# zero_board.net
KiCad netlist of a schematic drawn in EAGLE
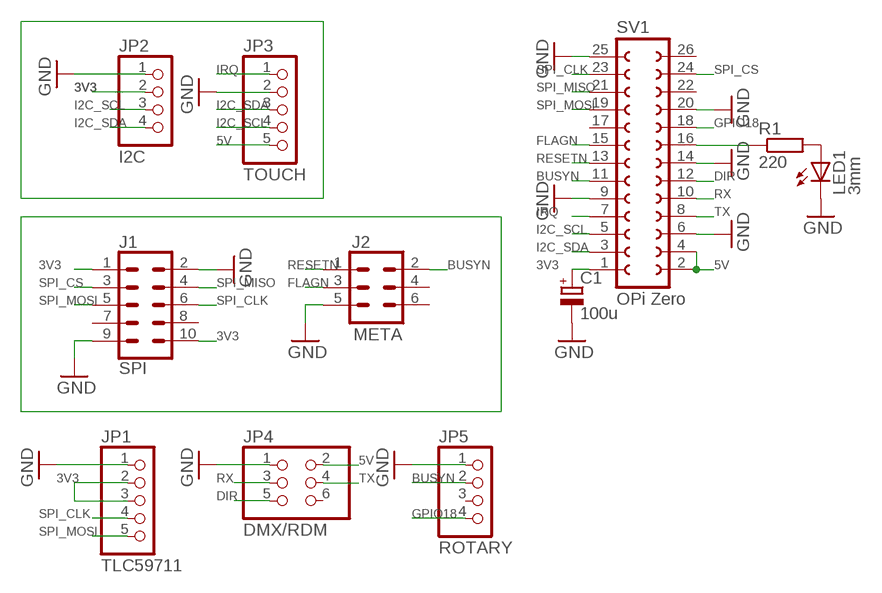
[diagram p0: schematic, sheet 1]

(export (version "E")
  (design (tool "Eeschema 10.0.6"))
  (components
    (comp (ref "C1")
      (value "100u")
      (footprint "eagle-import:E2,5-6")
      (libsource (lib "eagle-import") (part "CPOL-EUE2.5-6"))
    )
    (comp (ref "J1")
      (value "SPI")
      (footprint "eagle-import:2X5-SHROUDED")
      (libsource (lib "eagle-import") (part "CONN_05X2SHD"))
    )
    (comp (ref "J2")
      (value "META")
      (footprint "eagle-import:2X3-SHROUDED")
      (libsource (lib "eagle-import") (part "CONN_03X2SHROUD"))
    )
    (comp (ref "JP1")
      (value "TLC59711")
      (footprint "eagle-import:1X05")
      (libsource (lib "eagle-import") (part "PINHD-1X5"))
    )
    (comp (ref "JP2")
      (value "I2C")
      (footprint "eagle-import:1X04")
      (libsource (lib "eagle-import") (part "PINHD-1X4"))
    )
    (comp (ref "JP3")
      (value "TOUCH")
      (footprint "eagle-import:1X05")
      (libsource (lib "eagle-import") (part "PINHD-1X5"))
    )
    (comp (ref "JP4")
      (value "DMX/RDM")
      (footprint "eagle-import:2X03")
      (libsource (lib "eagle-import") (part "PINHD-2X3"))
    )
    (comp (ref "JP5")
      (value "ROTARY")
      (footprint "eagle-import:1X04")
      (libsource (lib "eagle-import") (part "PINHD-1X4"))
    )
    (comp (ref "LED1")
      (value "3mm")
      (footprint "eagle-import:LED3MM")
      (libsource (lib "eagle-import") (part "LED3MM"))
    )
    (comp (ref "R1")
      (value "220")
      (footprint "eagle-import:0204V")
      (libsource (lib "eagle-import") (part "R-EU_0204/2V"))
    )
    (comp (ref "SV1")
      (value "OPi Zero")
      (footprint "eagle-import:FE13-2")
      (libsource (lib "eagle-import") (part "FE13-2"))
    )
  )
  (nets
    (net (code "1") (name "/3V3") (class "Default")
      (node (ref "C1") (pin "+") (pinfunction "+_+") (pintype "passive"))
      (node (ref "J1") (pin "1") (pinfunction "1_1") (pintype "passive"))
      (node (ref "J1") (pin "10") (pinfunction "10_10") (pintype "passive"))
      (node (ref "JP1") (pin "2") (pinfunction "2_2") (pintype "passive"))
      (node (ref "JP1") (pin "3") (pinfunction "3_3") (pintype "passive"))
      (node (ref "JP2") (pin "2") (pinfunction "2_2") (pintype "passive"))
      (node (ref "SV1") (pin "1") (pinfunction "1_1") (pintype "passive"))
    )
    (net (code "2") (name "/5V") (class "Default")
      (node (ref "JP3") (pin "5") (pinfunction "5_5") (pintype "passive"))
      (node (ref "JP4") (pin "2") (pinfunction "2_2") (pintype "passive"))
      (node (ref "SV1") (pin "2") (pinfunction "2_2") (pintype "passive"))
      (node (ref "SV1") (pin "4") (pinfunction "4_4") (pintype "passive"))
    )
    (net (code "3") (name "/BUSYN") (class "Default")
      (node (ref "J2") (pin "2") (pinfunction "2_2") (pintype "bidirectional"))
      (node (ref "JP5") (pin "2") (pinfunction "2_2") (pintype "passive"))
      (node (ref "SV1") (pin "11") (pinfunction "11_11") (pintype "passive"))
    )
    (net (code "4") (name "/DIR") (class "Default")
      (node (ref "JP4") (pin "5") (pinfunction "5_5") (pintype "passive"))
      (node (ref "SV1") (pin "12") (pinfunction "12_12") (pintype "passive"))
    )
    (net (code "5") (name "/FLAGN") (class "Default")
      (node (ref "J2") (pin "3") (pinfunction "3_3") (pintype "bidirectional"))
      (node (ref "SV1") (pin "15") (pinfunction "15_15") (pintype "passive"))
    )
    (net (code "6") (name "/GPIO18") (class "Default")
      (node (ref "JP5") (pin "4") (pinfunction "4_4") (pintype "passive"))
      (node (ref "SV1") (pin "18") (pinfunction "18_18") (pintype "passive"))
    )
    (net (code "7") (name "/I2C_SCL") (class "Default")
      (node (ref "JP2") (pin "3") (pinfunction "3_3") (pintype "passive"))
      (node (ref "JP3") (pin "4") (pinfunction "4_4") (pintype "passive"))
      (node (ref "SV1") (pin "5") (pinfunction "5_5") (pintype "passive"))
    )
    (net (code "8") (name "/I2C_SDA") (class "Default")
      (node (ref "JP2") (pin "4") (pinfunction "4_4") (pintype "passive"))
      (node (ref "JP3") (pin "3") (pinfunction "3_3") (pintype "passive"))
      (node (ref "SV1") (pin "3") (pinfunction "3_3") (pintype "passive"))
    )
    (net (code "9") (name "/IRQ") (class "Default")
      (node (ref "JP3") (pin "1") (pinfunction "1_1") (pintype "passive"))
      (node (ref "SV1") (pin "7") (pinfunction "7_7") (pintype "passive"))
    )
    (net (code "10") (name "/RESETN") (class "Default")
      (node (ref "J2") (pin "1") (pinfunction "1_1") (pintype "bidirectional"))
      (node (ref "SV1") (pin "13") (pinfunction "13_13") (pintype "passive"))
    )
    (net (code "11") (name "/RX") (class "Default")
      (node (ref "JP4") (pin "3") (pinfunction "3_3") (pintype "passive"))
      (node (ref "SV1") (pin "10") (pinfunction "10_10") (pintype "passive"))
    )
    (net (code "12") (name "/SPI_CLK") (class "Default")
      (node (ref "J1") (pin "6") (pinfunction "6_6") (pintype "passive"))
      (node (ref "JP1") (pin "4") (pinfunction "4_4") (pintype "passive"))
      (node (ref "SV1") (pin "23") (pinfunction "23_23") (pintype "passive"))
    )
    (net (code "13") (name "/SPI_CS") (class "Default")
      (node (ref "J1") (pin "3") (pinfunction "3_3") (pintype "passive"))
      (node (ref "SV1") (pin "24") (pinfunction "24_24") (pintype "passive"))
    )
    (net (code "14") (name "/SPI_MISO") (class "Default")
      (node (ref "J1") (pin "4") (pinfunction "4_4") (pintype "passive"))
      (node (ref "SV1") (pin "21") (pinfunction "21_21") (pintype "passive"))
    )
    (net (code "15") (name "/SPI_MOSI") (class "Default")
      (node (ref "J1") (pin "5") (pinfunction "5_5") (pintype "passive"))
      (node (ref "JP1") (pin "5") (pinfunction "5_5") (pintype "passive"))
      (node (ref "SV1") (pin "19") (pinfunction "19_19") (pintype "passive"))
    )
    (net (code "16") (name "/TX") (class "Default")
      (node (ref "JP4") (pin "4") (pinfunction "4_4") (pintype "passive"))
      (node (ref "SV1") (pin "8") (pinfunction "8_8") (pintype "passive"))
    )
    (net (code "17") (name "GND") (class "Default")
      (node (ref "C1") (pin "-") (pinfunction "-_-") (pintype "passive"))
      (node (ref "J1") (pin "2") (pinfunction "2_2") (pintype "passive"))
      (node (ref "J1") (pin "9") (pinfunction "9_9") (pintype "passive"))
      (node (ref "J2") (pin "5") (pinfunction "5_5") (pintype "bidirectional"))
      (node (ref "JP1") (pin "1") (pinfunction "1_1") (pintype "passive"))
      (node (ref "JP2") (pin "1") (pinfunction "1_1") (pintype "passive"))
      (node (ref "JP3") (pin "2") (pinfunction "2_2") (pintype "passive"))
      (node (ref "JP4") (pin "1") (pinfunction "1_1") (pintype "passive"))
      (node (ref "JP5") (pin "1") (pinfunction "1_1") (pintype "passive"))
      (node (ref "LED1") (pin "K") (pinfunction "C_K") (pintype "passive"))
      (node (ref "SV1") (pin "14") (pinfunction "14_14") (pintype "passive"))
      (node (ref "SV1") (pin "20") (pinfunction "20_20") (pintype "passive"))
      (node (ref "SV1") (pin "25") (pinfunction "25_25") (pintype "passive"))
      (node (ref "SV1") (pin "6") (pinfunction "6_6") (pintype "passive"))
      (node (ref "SV1") (pin "9") (pinfunction "9_9") (pintype "passive"))
    )
    (net (code "18") (name "Net-(LED1-PadA)") (class "Default")
      (node (ref "LED1") (pin "A") (pinfunction "A_A") (pintype "passive"))
      (node (ref "R1") (pin "2") (pinfunction "2_2") (pintype "passive"))
    )
    (net (code "19") (name "Net-(R1-Pad1)") (class "Default")
      (node (ref "R1") (pin "1") (pinfunction "1_1") (pintype "passive"))
      (node (ref "SV1") (pin "16") (pinfunction "16_16") (pintype "passive"))
    )
    (net (code "20") (name "unconnected-(J1-Pad7)") (class "Default")
      (node (ref "J1") (pin "7") (pinfunction "7_7") (pintype "passive"))
    )
    (net (code "21") (name "unconnected-(J1-Pad8)") (class "Default")
      (node (ref "J1") (pin "8") (pinfunction "8_8") (pintype "passive"))
    )
    (net (code "22") (name "unconnected-(J2-Pad4)") (class "Default")
      (node (ref "J2") (pin "4") (pinfunction "4_4") (pintype "bidirectional"))
    )
    (net (code "23") (name "unconnected-(J2-Pad6)") (class "Default")
      (node (ref "J2") (pin "6") (pinfunction "6_6") (pintype "bidirectional"))
    )
    (net (code "24") (name "unconnected-(JP4-Pad6)") (class "Default")
      (node (ref "JP4") (pin "6") (pinfunction "6_6") (pintype "passive"))
    )
    (net (code "25") (name "unconnected-(JP5-Pad3)") (class "Default")
      (node (ref "JP5") (pin "3") (pinfunction "3_3") (pintype "passive"))
    )
    (net (code "26") (name "unconnected-(SV1-Pad17)") (class "Default")
      (node (ref "SV1") (pin "17") (pinfunction "17_17") (pintype "passive"))
    )
    (net (code "27") (name "unconnected-(SV1-Pad22)") (class "Default")
      (node (ref "SV1") (pin "22") (pinfunction "22_22") (pintype "passive"))
    )
    (net (code "28") (name "unconnected-(SV1-Pad26)") (class "Default")
      (node (ref "SV1") (pin "26") (pinfunction "26_26") (pintype "passive"))
    )
  )
)
